# Teensy_Stromzaehler.net
KiCad netlist of a schematic drawn in EAGLE
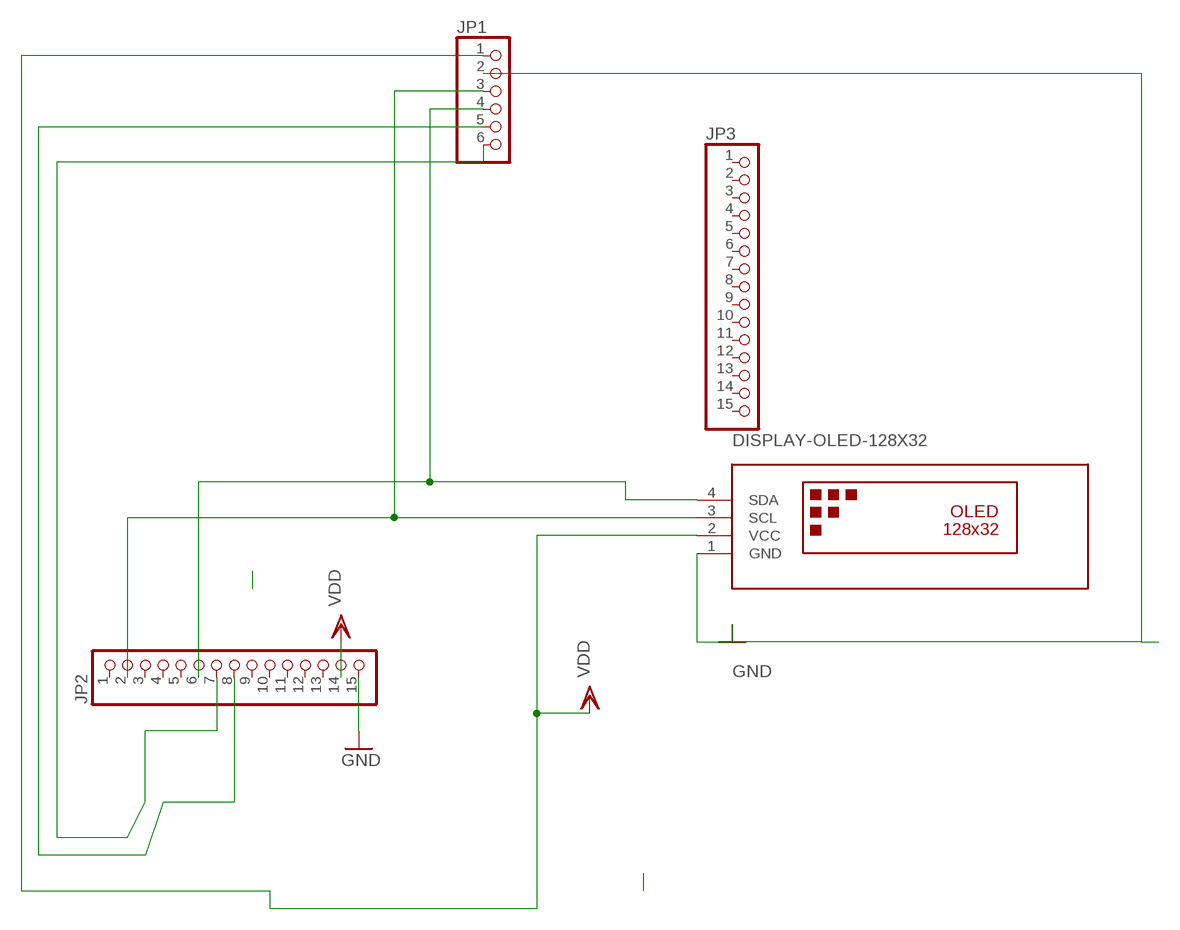
[diagram p0: schematic, sheet 1]

(export (version "E")
  (design (tool "Eeschema 10.0.6"))
  (components
    (comp (ref "JP1")
      (value "PINHD-1X6")
      (footprint "eagle-import:1X06")
      (libsource (lib "eagle-import") (part "PINHD-1X6"))
    )
    (comp (ref "JP2")
      (value "PINHD-1X15")
      (footprint "eagle-import:1X15")
      (libsource (lib "eagle-import") (part "PINHD-1X15"))
    )
    (comp (ref "JP3")
      (value "PINHD-1X15")
      (footprint "eagle-import:1X15")
      (libsource (lib "eagle-import") (part "PINHD-1X15"))
    )
    (comp (ref "U$3")
      (value "DISPLAY-OLED-128X32")
      (footprint "eagle-import:DISPLAY-OLED-128X32")
      (libsource (lib "eagle-import") (part "DISPLAY-OLED-128X32"))
    )
  )
  (nets
    (net (code "1") (name "GND") (class "Default")
      (node (ref "JP1") (pin "2") (pinfunction "2_2") (pintype "passive"))
      (node (ref "JP2") (pin "15") (pinfunction "15_15") (pintype "passive"))
      (node (ref "U$3") (pin "1") (pinfunction "GND_1") (pintype "power_in"))
    )
    (net (code "2") (name "Net-(JP1-Pad5)") (class "Default")
      (node (ref "JP1") (pin "5") (pinfunction "5_5") (pintype "passive"))
      (node (ref "JP2") (pin "8") (pinfunction "8_8") (pintype "passive"))
    )
    (net (code "3") (name "Net-(JP1-Pad6)") (class "Default")
      (node (ref "JP1") (pin "6") (pinfunction "6_6") (pintype "passive"))
      (node (ref "JP2") (pin "7") (pinfunction "7_7") (pintype "passive"))
    )
    (net (code "4") (name "Net-(U$3-SCL)") (class "Default")
      (node (ref "JP1") (pin "3") (pinfunction "3_3") (pintype "passive"))
      (node (ref "JP2") (pin "2") (pinfunction "2_2") (pintype "passive"))
      (node (ref "U$3") (pin "3") (pinfunction "SCL_3") (pintype "bidirectional"))
    )
    (net (code "5") (name "Net-(U$3-SDA)") (class "Default")
      (node (ref "JP1") (pin "4") (pinfunction "4_4") (pintype "passive"))
      (node (ref "JP2") (pin "6") (pinfunction "6_6") (pintype "passive"))
      (node (ref "U$3") (pin "4") (pinfunction "SDA_4") (pintype "bidirectional"))
    )
    (net (code "6") (name "VDD") (class "Default")
      (node (ref "JP1") (pin "1") (pinfunction "1_1") (pintype "passive"))
      (node (ref "JP2") (pin "14") (pinfunction "14_14") (pintype "passive"))
      (node (ref "U$3") (pin "2") (pinfunction "VCC_2") (pintype "power_in"))
    )
    (net (code "7") (name "unconnected-(JP2-Pad1)") (class "Default")
      (node (ref "JP2") (pin "1") (pinfunction "1_1") (pintype "passive"))
    )
    (net (code "8") (name "unconnected-(JP2-Pad3)") (class "Default")
      (node (ref "JP2") (pin "3") (pinfunction "3_3") (pintype "passive"))
    )
    (net (code "9") (name "unconnected-(JP2-Pad4)") (class "Default")
      (node (ref "JP2") (pin "4") (pinfunction "4_4") (pintype "passive"))
    )
    (net (code "10") (name "unconnected-(JP2-Pad5)") (class "Default")
      (node (ref "JP2") (pin "5") (pinfunction "5_5") (pintype "passive"))
    )
    (net (code "11") (name "unconnected-(JP2-Pad9)") (class "Default")
      (node (ref "JP2") (pin "9") (pinfunction "9_9") (pintype "passive"))
    )
    (net (code "12") (name "unconnected-(JP2-Pad10)") (class "Default")
      (node (ref "JP2") (pin "10") (pinfunction "10_10") (pintype "passive"))
    )
    (net (code "13") (name "unconnected-(JP2-Pad11)") (class "Default")
      (node (ref "JP2") (pin "11") (pinfunction "11_11") (pintype "passive"))
    )
    (net (code "14") (name "unconnected-(JP2-Pad12)") (class "Default")
      (node (ref "JP2") (pin "12") (pinfunction "12_12") (pintype "passive"))
    )
    (net (code "15") (name "unconnected-(JP2-Pad13)") (class "Default")
      (node (ref "JP2") (pin "13") (pinfunction "13_13") (pintype "passive"))
    )
    (net (code "16") (name "unconnected-(JP3-Pad1)") (class "Default")
      (node (ref "JP3") (pin "1") (pinfunction "1_1") (pintype "passive"))
    )
    (net (code "17") (name "unconnected-(JP3-Pad2)") (class "Default")
      (node (ref "JP3") (pin "2") (pinfunction "2_2") (pintype "passive"))
    )
    (net (code "18") (name "unconnected-(JP3-Pad3)") (class "Default")
      (node (ref "JP3") (pin "3") (pinfunction "3_3") (pintype "passive"))
    )
    (net (code "19") (name "unconnected-(JP3-Pad4)") (class "Default")
      (node (ref "JP3") (pin "4") (pinfunction "4_4") (pintype "passive"))
    )
    (net (code "20") (name "unconnected-(JP3-Pad5)") (class "Default")
      (node (ref "JP3") (pin "5") (pinfunction "5_5") (pintype "passive"))
    )
    (net (code "21") (name "unconnected-(JP3-Pad6)") (class "Default")
      (node (ref "JP3") (pin "6") (pinfunction "6_6") (pintype "passive"))
    )
    (net (code "22") (name "unconnected-(JP3-Pad7)") (class "Default")
      (node (ref "JP3") (pin "7") (pinfunction "7_7") (pintype "passive"))
    )
    (net (code "23") (name "unconnected-(JP3-Pad8)") (class "Default")
      (node (ref "JP3") (pin "8") (pinfunction "8_8") (pintype "passive"))
    )
    (net (code "24") (name "unconnected-(JP3-Pad9)") (class "Default")
      (node (ref "JP3") (pin "9") (pinfunction "9_9") (pintype "passive"))
    )
    (net (code "25") (name "unconnected-(JP3-Pad10)") (class "Default")
      (node (ref "JP3") (pin "10") (pinfunction "10_10") (pintype "passive"))
    )
    (net (code "26") (name "unconnected-(JP3-Pad11)") (class "Default")
      (node (ref "JP3") (pin "11") (pinfunction "11_11") (pintype "passive"))
    )
    (net (code "27") (name "unconnected-(JP3-Pad12)") (class "Default")
      (node (ref "JP3") (pin "12") (pinfunction "12_12") (pintype "passive"))
    )
    (net (code "28") (name "unconnected-(JP3-Pad13)") (class "Default")
      (node (ref "JP3") (pin "13") (pinfunction "13_13") (pintype "passive"))
    )
    (net (code "29") (name "unconnected-(JP3-Pad14)") (class "Default")
      (node (ref "JP3") (pin "14") (pinfunction "14_14") (pintype "passive"))
    )
    (net (code "30") (name "unconnected-(JP3-Pad15)") (class "Default")
      (node (ref "JP3") (pin "15") (pinfunction "15_15") (pintype "passive"))
    )
  )
)
